# ina199-current-sensor.net
KiCad netlist of a schematic drawn in EAGLE
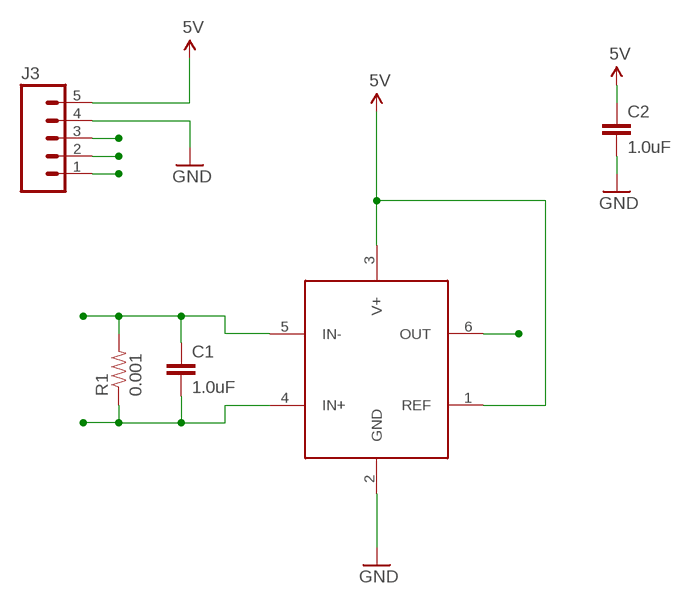
[diagram p0: schematic, sheet 1]

(export (version "E")
  (design (tool "Eeschema 10.0.6"))
  (components
    (comp (ref "C1")
      (value "1.0uF")
      (footprint "eagle-import:1206-CAP")
      (libsource (lib "eagle-import") (part "1.0UF50V10%(1206)"))
    )
    (comp (ref "C2")
      (value "1.0uF")
      (footprint "eagle-import:1206-CAP")
      (libsource (lib "eagle-import") (part "1.0UF50V10%(1206)"))
    )
    (comp (ref "J3")
      (value "M05LOCK_LONGPADS")
      (footprint "eagle-import:1X05_LOCK_LONGPADS")
      (libsource (lib "eagle-import") (part "M05LOCK_LONGPADS"))
    )
    (comp (ref "R1")
      (value "0.001")
      (footprint "eagle-import:2512")
      (libsource (lib "eagle-import") (part "0.001OHM-3W-1%(2512)3W/1%"))
    )
    (comp (ref "U$1")
      (value "INA199SC70")
      (footprint "eagle-import:SC70-6")
      (libsource (lib "eagle-import") (part "INA199SC70"))
    )
  )
  (nets
    (net (code "1") (name "/LOAD") (class "Default")
      (node (ref "C1") (pin "1") (pinfunction "1_1") (pintype "passive"))
      (node (ref "J3") (pin "2") (pinfunction "2_2") (pintype "passive"))
      (node (ref "R1") (pin "2") (pinfunction "2_2") (pintype "passive"))
      (node (ref "U$1") (pin "5") (pinfunction "IN-_5") (pintype "bidirectional"))
    )
    (net (code "2") (name "/OUT") (class "Default")
      (node (ref "J3") (pin "3") (pinfunction "3_3") (pintype "passive"))
      (node (ref "U$1") (pin "6") (pinfunction "OUT_6") (pintype "bidirectional"))
    )
    (net (code "3") (name "/SUPPLY") (class "Default")
      (node (ref "C1") (pin "2") (pinfunction "2_2") (pintype "passive"))
      (node (ref "J3") (pin "1") (pinfunction "1_1") (pintype "passive"))
      (node (ref "R1") (pin "1") (pinfunction "1_1") (pintype "passive"))
      (node (ref "U$1") (pin "4") (pinfunction "IN+_4") (pintype "bidirectional"))
    )
    (net (code "4") (name "5V") (class "Default")
      (node (ref "C2") (pin "1") (pinfunction "1_1") (pintype "passive"))
      (node (ref "J3") (pin "5") (pinfunction "5_5") (pintype "passive"))
      (node (ref "U$1") (pin "1") (pinfunction "REF_1") (pintype "bidirectional"))
      (node (ref "U$1") (pin "3") (pinfunction "V+_3") (pintype "bidirectional"))
    )
    (net (code "5") (name "GND") (class "Default")
      (node (ref "C2") (pin "2") (pinfunction "2_2") (pintype "passive"))
      (node (ref "J3") (pin "4") (pinfunction "4_4") (pintype "passive"))
      (node (ref "U$1") (pin "2") (pinfunction "GND_2") (pintype "bidirectional"))
    )
  )
)
